# LowCurrent.net
KiCad netlist of a schematic drawn in Altium Designer
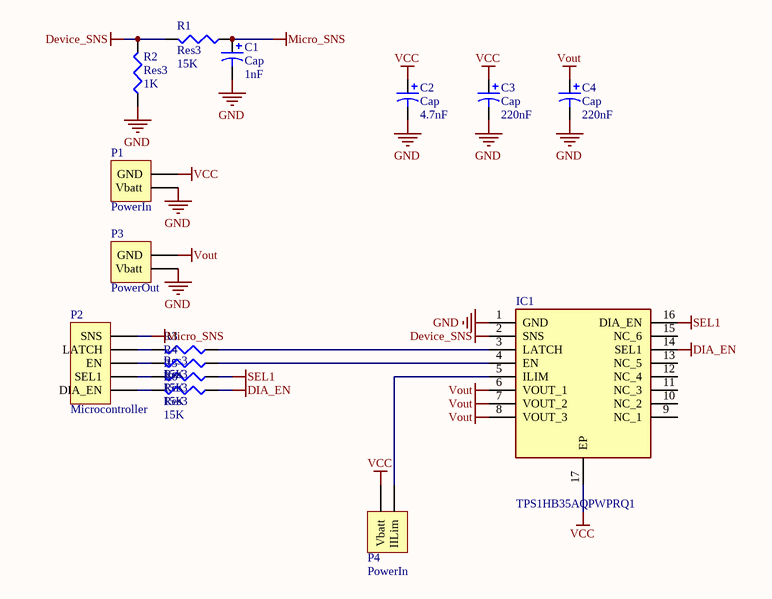
[diagram p0: LowCurrent.SchDoc]

(export (version "E")
  (design (tool "Eeschema 10.0.6"))
  (components
    (comp (ref "C1")
      (value "Cap")
      (footprint "C0805")
      (description "Polarized Capacitor (Surface Mount)")
      (fields (field (name "ALTIUM_VALUE") "1nF") (field (name "PUBLISHER") "Altium Limited"))
      (libsource (lib "Miscellaneous Devices") (part "Cap Pol3"))
    )
    (comp (ref "C2")
      (value "Cap")
      (footprint "C0805")
      (description "Polarized Capacitor (Surface Mount)")
      (fields (field (name "ALTIUM_VALUE") "4.7nF") (field (name "PUBLISHER") "Altium Limited"))
      (libsource (lib "Miscellaneous Devices") (part "Cap Pol3"))
    )
    (comp (ref "C3")
      (value "Cap")
      (footprint "C0805")
      (description "Polarized Capacitor (Surface Mount)")
      (fields (field (name "ALTIUM_VALUE") "220nF") (field (name "PUBLISHER") "Altium Limited"))
      (libsource (lib "Miscellaneous Devices") (part "Cap Pol3"))
    )
    (comp (ref "C4")
      (value "Cap")
      (footprint "C0805")
      (description "Polarized Capacitor (Surface Mount)")
      (fields (field (name "ALTIUM_VALUE") "220nF") (field (name "PUBLISHER") "Altium Limited"))
      (libsource (lib "Miscellaneous Devices") (part "Cap Pol3"))
    )
    (comp (ref "IC1")
      (value "TPS1HB35AQPWPRQ1")
      (footprint "SamacSys:SOP65P640X120-17N")
      (description "Integrated Circuit")
      (fields (field (name "MOUSER PART NUMBER") "595-TPS1HB35AQPWPRQ1"))
      (libsource (lib "*") (part "TPS1HB35AQPWPRQ1"))
    )
    (comp (ref "P1")
      (value "PowerIn")
      (footprint "HDR1X2")
      (description "Power Header")
      (fields (field (name "PUBLISHER") "Altium Limited"))
      (libsource (lib "Miscellaneous Connectors") (part "Header 2"))
    )
    (comp (ref "P2")
      (value "Microcontroller")
      (footprint "HDR1X5")
      (description "Header, 5-Pin")
      (fields (field (name "PUBLISHER") "Altium Limited"))
      (libsource (lib "Miscellaneous Connectors") (part "Header 5"))
    )
    (comp (ref "P3")
      (value "PowerOut")
      (footprint "HDR1X2")
      (description "Power Header")
      (fields (field (name "PUBLISHER") "Altium Limited"))
      (libsource (lib "Miscellaneous Connectors") (part "Header 2"))
    )
    (comp (ref "P4")
      (value "PowerIn")
      (footprint "HDR1X2")
      (description "Power Header")
      (fields (field (name "PUBLISHER") "Altium Limited"))
      (libsource (lib "") (part "Header 2_1"))
    )
    (comp (ref "R1")
      (value "Res3")
      (footprint "J1-0603")
      (description "Resistor")
      (fields (field (name "ALTIUM_VALUE") "15K") (field (name "PUBLISHER") "Altium Limited"))
      (libsource (lib "Miscellaneous Devices") (part "Res3"))
    )
    (comp (ref "R2")
      (value "Res3")
      (footprint "J1-0603")
      (description "Resistor")
      (fields (field (name "ALTIUM_VALUE") "1K") (field (name "PUBLISHER") "Altium Limited"))
      (libsource (lib "Miscellaneous Devices") (part "Res3"))
    )
    (comp (ref "R3")
      (value "Res3")
      (footprint "J1-0603")
      (description "Resistor")
      (fields (field (name "ALTIUM_VALUE") "15K") (field (name "PUBLISHER") "Altium Limited"))
      (libsource (lib "Miscellaneous Devices") (part "Res3"))
    )
    (comp (ref "R4")
      (value "Res3")
      (footprint "J1-0603")
      (description "Resistor")
      (fields (field (name "ALTIUM_VALUE") "15K") (field (name "PUBLISHER") "Altium Limited"))
      (libsource (lib "Miscellaneous Devices") (part "Res3"))
    )
    (comp (ref "R5")
      (value "Res3")
      (footprint "J1-0603")
      (description "Resistor")
      (fields (field (name "ALTIUM_VALUE") "15K") (field (name "PUBLISHER") "Altium Limited"))
      (libsource (lib "Miscellaneous Devices") (part "Res3"))
    )
    (comp (ref "R6")
      (value "Res3")
      (footprint "J1-0603")
      (description "Resistor")
      (fields (field (name "ALTIUM_VALUE") "15K") (field (name "PUBLISHER") "Altium Limited"))
      (libsource (lib "Miscellaneous Devices") (part "Res3"))
    )
  )
  (nets
    (net (code "1") (name "DIA_EN") (class "Default")
      (node (ref "IC1") (pin "14") (pinfunction "SEL1_14") (pintype "passive"))
      (node (ref "R6") (pin "1") (pinfunction "1_1") (pintype "passive"))
    )
    (net (code "2") (name "Device_SNS") (class "Default")
      (node (ref "IC1") (pin "2") (pinfunction "SNS_2") (pintype "passive"))
      (node (ref "R1") (pin "2") (pinfunction "2_2") (pintype "passive"))
      (node (ref "R2") (pin "2") (pinfunction "2_2") (pintype "passive"))
    )
    (net (code "3") (name "GND") (class "Default")
      (node (ref "C1") (pin "2") (pinfunction "2_2") (pintype "passive"))
      (node (ref "C2") (pin "2") (pinfunction "2_2") (pintype "passive"))
      (node (ref "C3") (pin "2") (pinfunction "2_2") (pintype "passive"))
      (node (ref "C4") (pin "2") (pinfunction "2_2") (pintype "passive"))
      (node (ref "IC1") (pin "1") (pinfunction "GND_1") (pintype "passive"))
      (node (ref "P1") (pin "1") (pinfunction "Vbatt_1") (pintype "passive"))
      (node (ref "P3") (pin "1") (pinfunction "Vbatt_1") (pintype "passive"))
      (node (ref "R2") (pin "1") (pinfunction "1_1") (pintype "passive"))
    )
    (net (code "4") (name "Micro_SNS") (class "Default")
      (node (ref "C1") (pin "1") (pinfunction "1_1") (pintype "passive"))
      (node (ref "P2") (pin "1") (pinfunction "SNS_1") (pintype "passive"))
      (node (ref "R1") (pin "1") (pinfunction "1_1") (pintype "passive"))
    )
    (net (code "5") (name "Net-(IC1-EN)") (class "Default")
      (node (ref "IC1") (pin "4") (pinfunction "EN_4") (pintype "passive"))
      (node (ref "R4") (pin "1") (pinfunction "1_1") (pintype "passive"))
    )
    (net (code "6") (name "Net-(IC1-ILIM)") (class "Default")
      (node (ref "IC1") (pin "5") (pinfunction "ILIM_5") (pintype "passive"))
      (node (ref "P4") (pin "1") (pinfunction "IILim_1") (pintype "passive"))
    )
    (net (code "7") (name "Net-(IC1-LATCH)") (class "Default")
      (node (ref "IC1") (pin "3") (pinfunction "LATCH_3") (pintype "passive"))
      (node (ref "R3") (pin "1") (pinfunction "1_1") (pintype "passive"))
    )
    (net (code "8") (name "Net-(P2-DIA_EN)") (class "Default")
      (node (ref "P2") (pin "5") (pinfunction "DIA_EN_5") (pintype "passive"))
      (node (ref "R6") (pin "2") (pinfunction "2_2") (pintype "passive"))
    )
    (net (code "9") (name "Net-(P2-EN)") (class "Default")
      (node (ref "P2") (pin "3") (pinfunction "EN_3") (pintype "passive"))
      (node (ref "R4") (pin "2") (pinfunction "2_2") (pintype "passive"))
    )
    (net (code "10") (name "Net-(P2-LATCH)") (class "Default")
      (node (ref "P2") (pin "2") (pinfunction "LATCH_2") (pintype "passive"))
      (node (ref "R3") (pin "2") (pinfunction "2_2") (pintype "passive"))
    )
    (net (code "11") (name "Net-(P2-SEL1)") (class "Default")
      (node (ref "P2") (pin "4") (pinfunction "SEL1_4") (pintype "passive"))
      (node (ref "R5") (pin "2") (pinfunction "2_2") (pintype "passive"))
    )
    (net (code "12") (name "SEL1") (class "Default")
      (node (ref "IC1") (pin "16") (pinfunction "DIA_EN_16") (pintype "passive"))
      (node (ref "R5") (pin "1") (pinfunction "1_1") (pintype "passive"))
    )
    (net (code "13") (name "VCC") (class "Default")
      (node (ref "C2") (pin "1") (pinfunction "1_1") (pintype "passive"))
      (node (ref "C3") (pin "1") (pinfunction "1_1") (pintype "passive"))
      (node (ref "IC1") (pin "17") (pinfunction "EP_17") (pintype "passive"))
      (node (ref "P1") (pin "2") (pinfunction "GND_2") (pintype "passive"))
      (node (ref "P4") (pin "2") (pinfunction "Vbatt_2") (pintype "passive"))
    )
    (net (code "14") (name "Vout") (class "Default")
      (node (ref "C4") (pin "1") (pinfunction "1_1") (pintype "passive"))
      (node (ref "IC1") (pin "6") (pinfunction "VOUT_1_6") (pintype "passive"))
      (node (ref "IC1") (pin "7") (pinfunction "VOUT_2_7") (pintype "passive"))
      (node (ref "IC1") (pin "8") (pinfunction "VOUT_3_8") (pintype "passive"))
      (node (ref "P3") (pin "2") (pinfunction "GND_2") (pintype "passive"))
    )
    (net (code "15") (name "unconnected-(IC1-NC_1-Pad9)") (class "Default")
      (node (ref "IC1") (pin "9") (pinfunction "NC_1_9") (pintype "passive"))
    )
    (net (code "16") (name "unconnected-(IC1-NC_2-Pad10)") (class "Default")
      (node (ref "IC1") (pin "10") (pinfunction "NC_2_10") (pintype "passive"))
    )
    (net (code "17") (name "unconnected-(IC1-NC_3-Pad11)") (class "Default")
      (node (ref "IC1") (pin "11") (pinfunction "NC_3_11") (pintype "passive"))
    )
    (net (code "18") (name "unconnected-(IC1-NC_4-Pad12)") (class "Default")
      (node (ref "IC1") (pin "12") (pinfunction "NC_4_12") (pintype "passive"))
    )
    (net (code "19") (name "unconnected-(IC1-NC_5-Pad13)") (class "Default")
      (node (ref "IC1") (pin "13") (pinfunction "NC_5_13") (pintype "passive"))
    )
    (net (code "20") (name "unconnected-(IC1-NC_6-Pad15)") (class "Default")
      (node (ref "IC1") (pin "15") (pinfunction "NC_6_15") (pintype "passive"))
    )
  )
)
